# SCH_ESP_toster_GPIOv2.net
KiCad netlist of a schematic drawn in EasyEDA
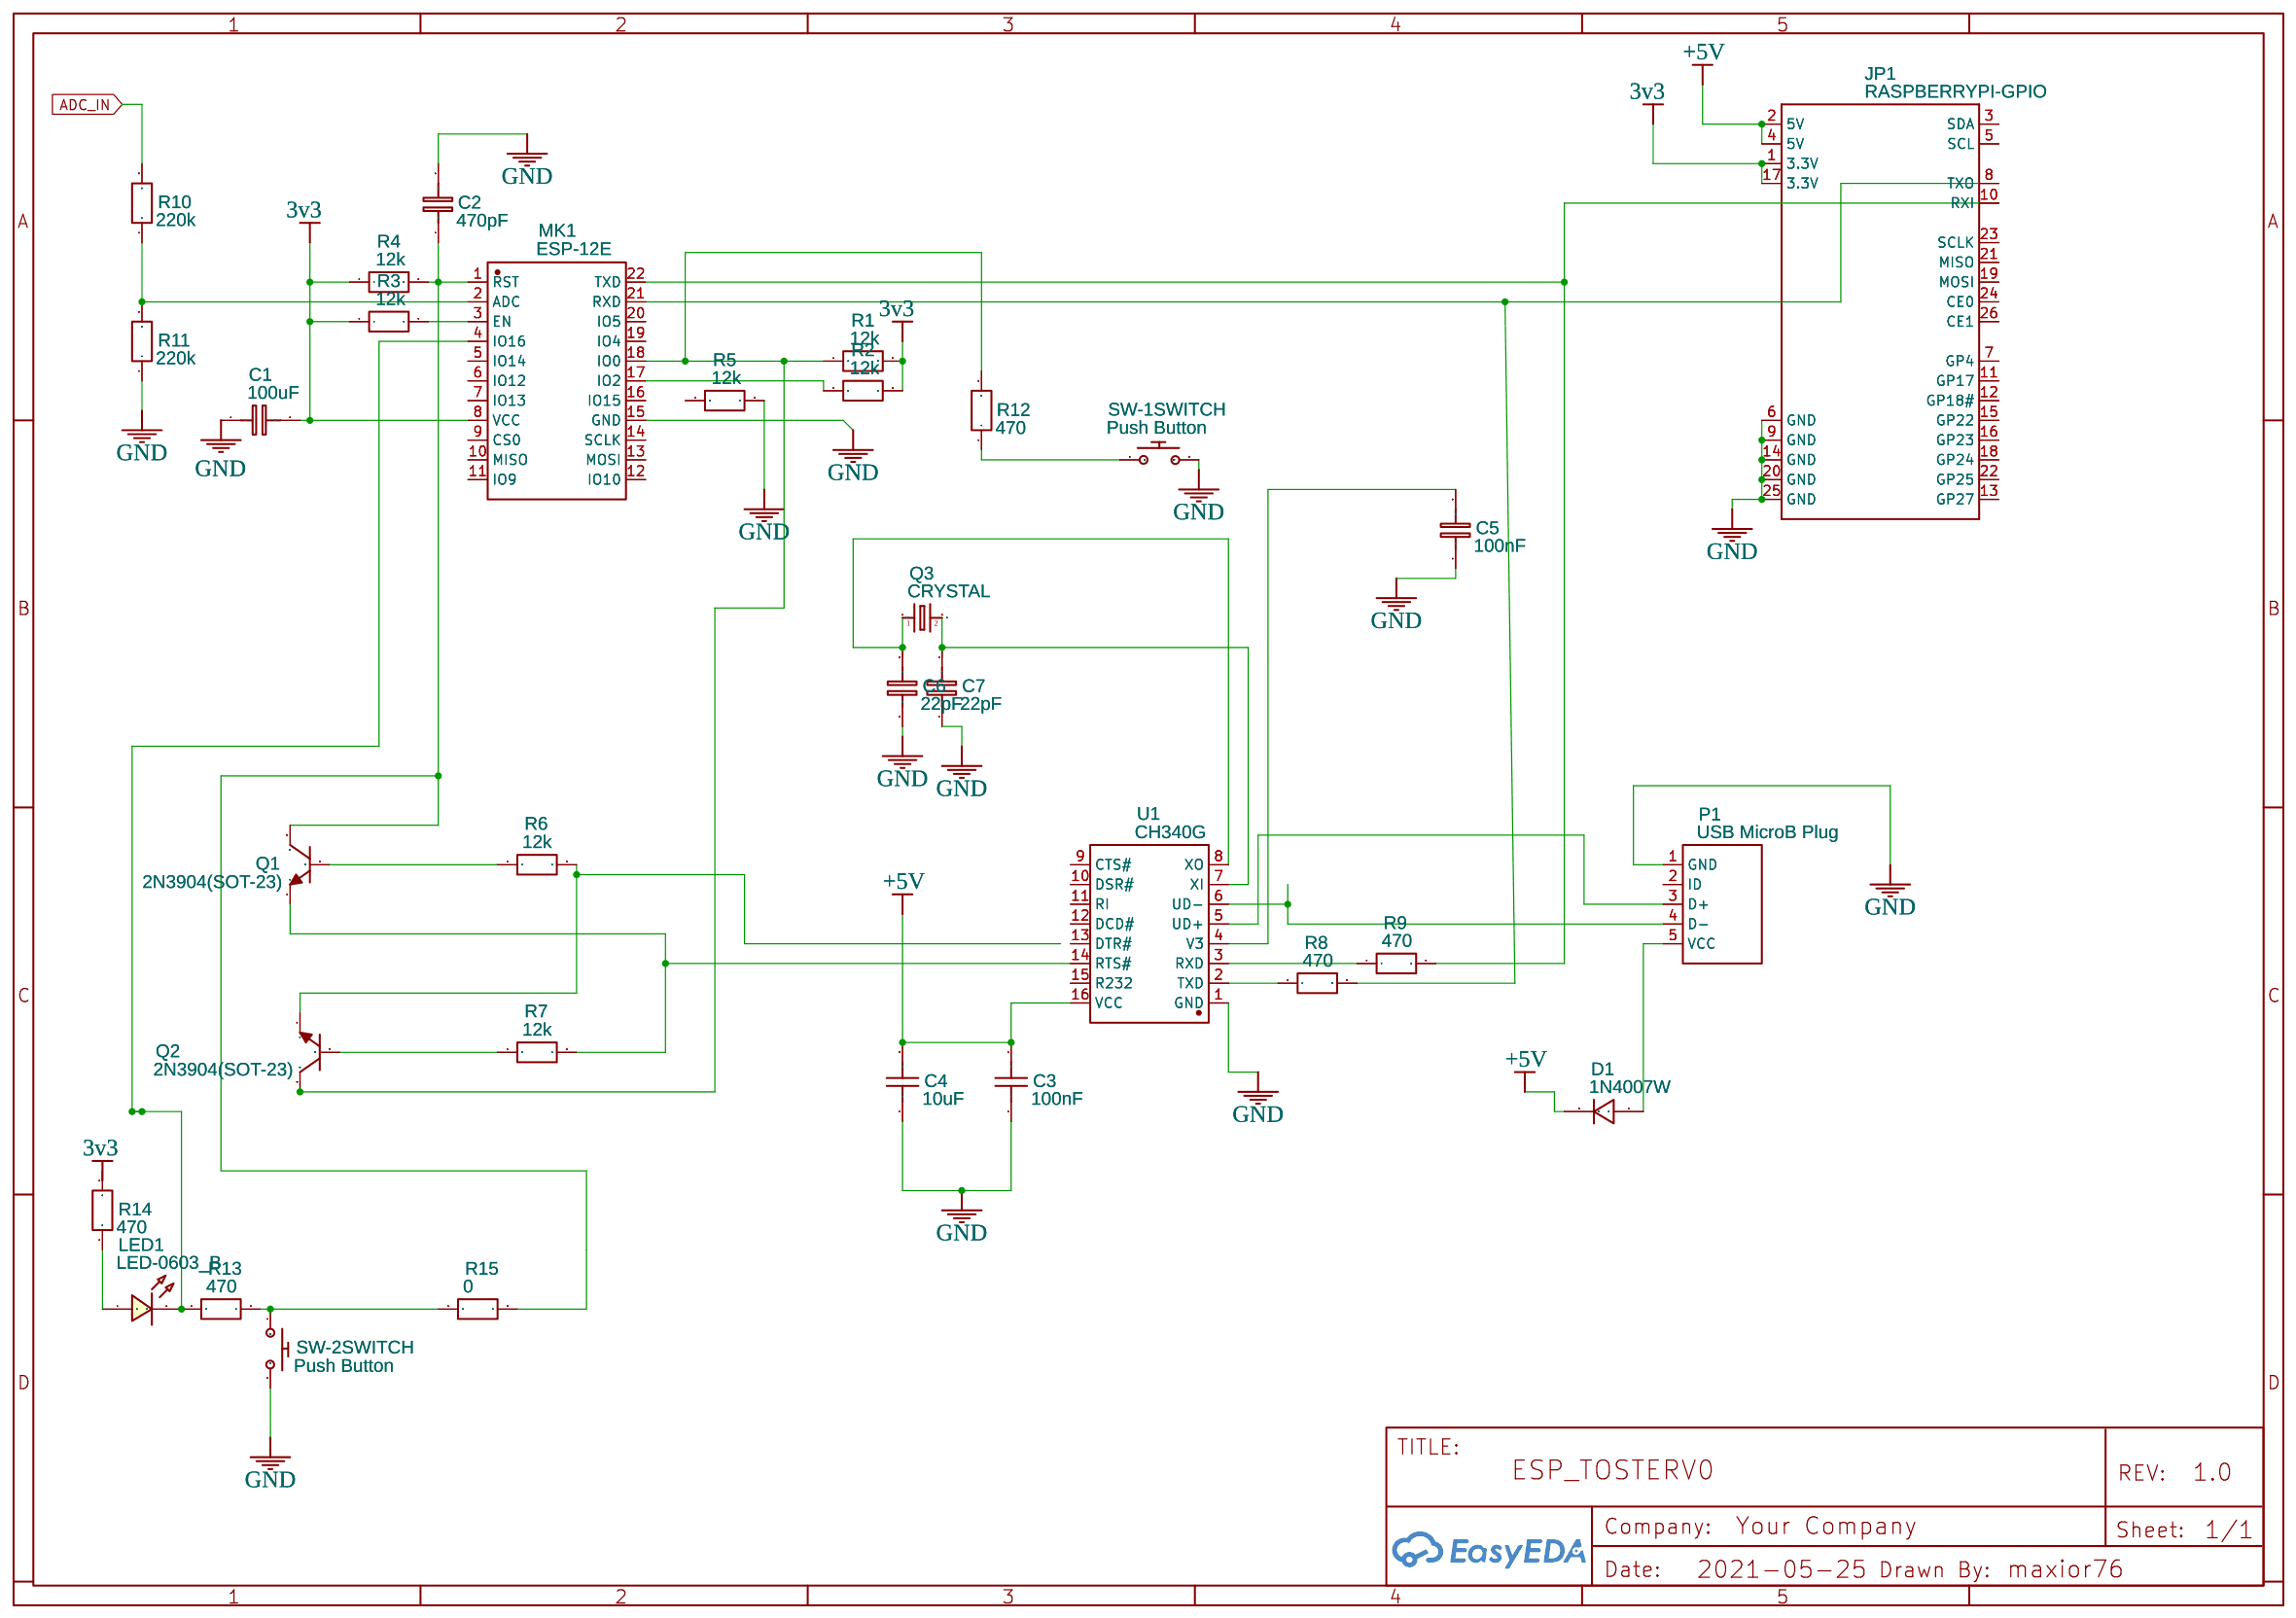
[diagram p0: schematic sheet]

(export (version "E")
  (design (tool "Eeschema 10.0.6"))
  (components
    (comp (ref "C1") (value "100uF") (libsource (lib "") (part "C_0603_EU_3")))
    (comp (ref "C2") (value "470pF") (libsource (lib "") (part "C_0603_EU")))
    (comp (ref "C3") (value "100nF") (libsource (lib "") (part "C_0603_US")))
    (comp (ref "C4") (value "10uF") (libsource (lib "") (part "C_0603_US")))
    (comp (ref "C5") (value "100nF") (libsource (lib "") (part "C_0603_EU_2")))
    (comp (ref "C6") (value "22pF") (libsource (lib "") (part "C_0603_EU_1")))
    (comp (ref "C7") (value "22pF") (libsource (lib "") (part "C_0603_EU_1")))
    (comp (ref "D1")
      (value "1N4007W")
      (fields (field (name "BOM_Supplier Part") "C328592"))
      (libsource (lib "") (part "1N4007W"))
    )
    (comp (ref "JP1") (value "RASPBERRYPI-GPIO") (libsource (lib "") (part "RASPBERRYPI-GPIO")))
    (comp (ref "LED1")
      (value "LED-0603_B")
      (fields
        (field (name "BOM_Manufacturer Part") "19-217/R6C-AL1M2VY/3T")
        (field (name "BOM_Supplier Part") "C72044")
      )
      (libsource (lib "") (part "LED-0603_R"))
    )
    (comp (ref "MK1")
      (value "ESP-12E")
      (fields (field (name "BOM_Supplier Part") "C89297"))
      (libsource (lib "") (part "ESP-12E"))
    )
    (comp (ref "P1") (value "USB MicroB Plug") (libsource (lib "") (part "USB MicroB Plug")))
    (comp (ref "Q1")
      (value "2N3904(SOT-23)")
      (fields
        (field (name "BOM_Manufacturer Part") "2n3904S-RTK/PS")
        (field (name "BOM_Supplier Part") "C18536")
      )
      (libsource (lib "") (part "2N3904(SOT-23)_1"))
    )
    (comp (ref "Q2")
      (value "2N3904(SOT-23)")
      (fields
        (field (name "BOM_Manufacturer Part") "2n3904S-RTK/PS")
        (field (name "BOM_Supplier Part") "C18536")
      )
      (libsource (lib "") (part "2N3904(SOT-23)"))
    )
    (comp (ref "Q3") (value "CRYSTAL") (libsource (lib "") (part "CRYSTAL")))
    (comp (ref "R1") (value "12k") (libsource (lib "") (part "R_0603_EU_1")))
    (comp (ref "R2") (value "12k") (libsource (lib "") (part "R_0603_EU_1")))
    (comp (ref "R3") (value "12k") (libsource (lib "") (part "R_0603_EU_1")))
    (comp (ref "R4") (value "12k") (libsource (lib "") (part "R_0603_EU_1")))
    (comp (ref "R5") (value "12k") (libsource (lib "") (part "R_0603_EU_1")))
    (comp (ref "R6") (value "12k") (libsource (lib "") (part "R_0603_EU_1")))
    (comp (ref "R7") (value "12k") (libsource (lib "") (part "R_0603_EU_1")))
    (comp (ref "R8") (value "470") (libsource (lib "") (part "R_0603_EU_1")))
    (comp (ref "R9") (value "470") (libsource (lib "") (part "R_0603_EU_1")))
    (comp (ref "R10") (value "220k") (libsource (lib "") (part "R_0603_EU")))
    (comp (ref "R11") (value "220k") (libsource (lib "") (part "R_0603_EU")))
    (comp (ref "R12") (value "470") (libsource (lib "") (part "R_0603_EU")))
    (comp (ref "R13") (value "470") (libsource (lib "") (part "R_0603_EU_1")))
    (comp (ref "R14") (value "470") (libsource (lib "") (part "R_0603_EU")))
    (comp (ref "R15") (value "0") (libsource (lib "") (part "R_0603_EU_1")))
    (comp (ref "SW-1SWITCH")
      (value "Push Button")
      (fields (field (name "BOM_Supplier Part") "COM-08720"))
      (libsource (lib "") (part "Push Button_1"))
    )
    (comp (ref "SW-2SWITCH")
      (value "Push Button")
      (fields (field (name "BOM_Supplier Part") "COM-08720"))
      (libsource (lib "") (part "Push Button"))
    )
    (comp (ref "U1")
      (value "CH340G")
      (fields (field (name "BOM_Supplier Part") "C14267"))
      (libsource (lib "") (part "CH340G"))
    )
  )
  (nets
    (net (code "1") (name "+5V") (class "Default")
      (node (ref "C3") (pin "2") (pinfunction "2_2") (pintype "unspecified"))
      (node (ref "C4") (pin "2") (pinfunction "2_2") (pintype "unspecified"))
      (node (ref "D1") (pin "1") (pinfunction "1_1") (pintype "unspecified"))
      (node (ref "JP1") (pin "2") (pinfunction "5V_2") (pintype "passive"))
      (node (ref "JP1") (pin "4") (pinfunction "5V_4") (pintype "passive"))
      (node (ref "U1") (pin "16") (pinfunction "VCC_16") (pintype "unspecified"))
    )
    (net (code "2") (name "3v3") (class "Default")
      (node (ref "C1") (pin "2") (pinfunction "2_2") (pintype "unspecified"))
      (node (ref "JP1") (pin "1") (pinfunction "3.3V_1") (pintype "passive"))
      (node (ref "JP1") (pin "17") (pinfunction "3.3V_17") (pintype "passive"))
      (node (ref "MK1") (pin "8") (pinfunction "VCC_8") (pintype "unspecified"))
      (node (ref "R1") (pin "2") (pinfunction "2_2") (pintype "unspecified"))
      (node (ref "R14") (pin "2") (pinfunction "2_2") (pintype "unspecified"))
      (node (ref "R2") (pin "2") (pinfunction "2_2") (pintype "unspecified"))
      (node (ref "R3") (pin "1") (pinfunction "1_1") (pintype "unspecified"))
      (node (ref "R4") (pin "1") (pinfunction "1_1") (pintype "unspecified"))
    )
    (net (code "3") (name "ADC_IN") (class "Default")
      (node (ref "R10") (pin "2") (pinfunction "2_2") (pintype "unspecified"))
    )
    (net (code "4") (name "GND") (class "Default")
      (node (ref "C1") (pin "1") (pinfunction "1_1") (pintype "unspecified"))
      (node (ref "C2") (pin "2") (pinfunction "2_2") (pintype "unspecified"))
      (node (ref "C3") (pin "1") (pinfunction "1_1") (pintype "unspecified"))
      (node (ref "C4") (pin "1") (pinfunction "1_1") (pintype "unspecified"))
      (node (ref "C5") (pin "1") (pinfunction "1_1") (pintype "unspecified"))
      (node (ref "C6") (pin "1") (pinfunction "1_1") (pintype "unspecified"))
      (node (ref "C7") (pin "1") (pinfunction "1_1") (pintype "unspecified"))
      (node (ref "JP1") (pin "14") (pinfunction "GND_14") (pintype "passive"))
      (node (ref "JP1") (pin "20") (pinfunction "GND_20") (pintype "passive"))
      (node (ref "JP1") (pin "25") (pinfunction "GND_25") (pintype "passive"))
      (node (ref "JP1") (pin "6") (pinfunction "GND_6") (pintype "passive"))
      (node (ref "JP1") (pin "9") (pinfunction "GND_9") (pintype "passive"))
      (node (ref "MK1") (pin "15") (pinfunction "GND_15") (pintype "unspecified"))
      (node (ref "P1") (pin "1") (pinfunction "GND_1") (pintype "unspecified"))
      (node (ref "R11") (pin "1") (pinfunction "1_1") (pintype "unspecified"))
      (node (ref "R5") (pin "2") (pinfunction "2_2") (pintype "unspecified"))
      (node (ref "SW-1SWITCH") (pin "2") (pinfunction "P$2_2") (pintype "unspecified"))
      (node (ref "SW-2SWITCH") (pin "2") (pinfunction "P$2_2") (pintype "unspecified"))
      (node (ref "U1") (pin "1") (pinfunction "GND_1") (pintype "unspecified"))
    )
    (net (code "5") (name "Net-(JP1-RXI)") (class "Default")
      (node (ref "JP1") (pin "10") (pinfunction "RXI_10") (pintype "input"))
      (node (ref "MK1") (pin "22") (pinfunction "TXD_22") (pintype "unspecified"))
      (node (ref "R9") (pin "2") (pinfunction "2_2") (pintype "unspecified"))
    )
    (net (code "6") (name "Net-(JP1-TXO)") (class "Default")
      (node (ref "JP1") (pin "8") (pinfunction "TXO_8") (pintype "output"))
      (node (ref "MK1") (pin "21") (pinfunction "RXD_21") (pintype "unspecified"))
      (node (ref "R8") (pin "2") (pinfunction "2_2") (pintype "unspecified"))
    )
    (net (code "7") (name "Net-(LED1-Pad1)") (class "Default")
      (node (ref "LED1") (pin "1") (pinfunction "1_1") (pintype "unspecified"))
      (node (ref "R14") (pin "1") (pinfunction "1_1") (pintype "unspecified"))
    )
    (net (code "8") (name "Net-(MK1-ADC)") (class "Default")
      (node (ref "MK1") (pin "2") (pinfunction "ADC_2") (pintype "unspecified"))
      (node (ref "R10") (pin "1") (pinfunction "1_1") (pintype "unspecified"))
      (node (ref "R11") (pin "2") (pinfunction "2_2") (pintype "unspecified"))
    )
    (net (code "9") (name "Net-(MK1-EN)") (class "Default")
      (node (ref "MK1") (pin "3") (pinfunction "EN_3") (pintype "unspecified"))
      (node (ref "R3") (pin "2") (pinfunction "2_2") (pintype "unspecified"))
    )
    (net (code "10") (name "Net-(MK1-IO0)") (class "Default")
      (node (ref "MK1") (pin "18") (pinfunction "IO0_18") (pintype "unspecified"))
      (node (ref "Q2") (pin "3") (pinfunction "C_3") (pintype "input"))
      (node (ref "R1") (pin "1") (pinfunction "1_1") (pintype "unspecified"))
      (node (ref "R12") (pin "2") (pinfunction "2_2") (pintype "unspecified"))
    )
    (net (code "11") (name "Net-(MK1-IO2)") (class "Default")
      (node (ref "MK1") (pin "17") (pinfunction "IO2_17") (pintype "unspecified"))
      (node (ref "R2") (pin "1") (pinfunction "1_1") (pintype "unspecified"))
    )
    (net (code "12") (name "Net-(MK1-IO16)") (class "Default")
      (node (ref "LED1") (pin "2") (pinfunction "2_2") (pintype "unspecified"))
      (node (ref "MK1") (pin "4") (pinfunction "IO16_4") (pintype "unspecified"))
      (node (ref "R13") (pin "1") (pinfunction "1_1") (pintype "unspecified"))
    )
    (net (code "13") (name "Net-(MK1-RST)") (class "Default")
      (node (ref "C2") (pin "1") (pinfunction "1_1") (pintype "unspecified"))
      (node (ref "MK1") (pin "1") (pinfunction "RST_1") (pintype "unspecified"))
      (node (ref "Q1") (pin "3") (pinfunction "C_3") (pintype "input"))
      (node (ref "R15") (pin "2") (pinfunction "2_2") (pintype "unspecified"))
      (node (ref "R4") (pin "2") (pinfunction "2_2") (pintype "unspecified"))
    )
    (net (code "14") (name "Net-(P1-D+)") (class "Default")
      (node (ref "P1") (pin "3") (pinfunction "D+_3") (pintype "unspecified"))
      (node (ref "U1") (pin "5") (pinfunction "UD+_5") (pintype "unspecified"))
    )
    (net (code "15") (name "Net-(P1-D-)") (class "Default")
      (node (ref "P1") (pin "4") (pinfunction "D-_4") (pintype "unspecified"))
      (node (ref "U1") (pin "6") (pinfunction "UD-_6") (pintype "unspecified"))
    )
    (net (code "16") (name "Net-(P1-VCC)") (class "Default")
      (node (ref "D1") (pin "2") (pinfunction "2_2") (pintype "unspecified"))
      (node (ref "P1") (pin "5") (pinfunction "VCC_5") (pintype "unspecified"))
    )
    (net (code "17") (name "Net-(Q1-B)") (class "Default")
      (node (ref "Q1") (pin "2") (pinfunction "B_2") (pintype "input"))
      (node (ref "R6") (pin "1") (pinfunction "1_1") (pintype "unspecified"))
    )
    (net (code "18") (name "Net-(Q1-E)") (class "Default")
      (node (ref "Q1") (pin "1") (pinfunction "E_1") (pintype "input"))
      (node (ref "R7") (pin "2") (pinfunction "2_2") (pintype "unspecified"))
      (node (ref "U1") (pin "14") (pinfunction "RTS#_14") (pintype "unspecified"))
    )
    (net (code "19") (name "Net-(Q2-B)") (class "Default")
      (node (ref "Q2") (pin "2") (pinfunction "B_2") (pintype "input"))
      (node (ref "R7") (pin "1") (pinfunction "1_1") (pintype "unspecified"))
    )
    (net (code "20") (name "Net-(Q2-E)") (class "Default")
      (node (ref "Q2") (pin "1") (pinfunction "E_1") (pintype "input"))
      (node (ref "R6") (pin "2") (pinfunction "2_2") (pintype "unspecified"))
    )
    (net (code "21") (name "Net-(SW-1SWITCH-P$1)") (class "Default")
      (node (ref "R12") (pin "1") (pinfunction "1_1") (pintype "unspecified"))
      (node (ref "SW-1SWITCH") (pin "1") (pinfunction "P$1_1") (pintype "unspecified"))
    )
    (net (code "22") (name "Net-(SW-2SWITCH-P$1)") (class "Default")
      (node (ref "R13") (pin "2") (pinfunction "2_2") (pintype "unspecified"))
      (node (ref "R15") (pin "1") (pinfunction "1_1") (pintype "unspecified"))
      (node (ref "SW-2SWITCH") (pin "1") (pinfunction "P$1_1") (pintype "unspecified"))
    )
    (net (code "23") (name "Net-(U1-RXD)") (class "Default")
      (node (ref "R9") (pin "1") (pinfunction "1_1") (pintype "unspecified"))
      (node (ref "U1") (pin "3") (pinfunction "RXD_3") (pintype "unspecified"))
    )
    (net (code "24") (name "Net-(U1-TXD)") (class "Default")
      (node (ref "R8") (pin "1") (pinfunction "1_1") (pintype "unspecified"))
      (node (ref "U1") (pin "2") (pinfunction "TXD_2") (pintype "unspecified"))
    )
    (net (code "25") (name "Net-(U1-V3)") (class "Default")
      (node (ref "C5") (pin "2") (pinfunction "2_2") (pintype "unspecified"))
      (node (ref "U1") (pin "4") (pinfunction "V3_4") (pintype "unspecified"))
    )
    (net (code "26") (name "Net-(U1-XI)") (class "Default")
      (node (ref "C7") (pin "2") (pinfunction "2_2") (pintype "unspecified"))
      (node (ref "Q3") (pin "2") (pinfunction "2_2") (pintype "unspecified"))
      (node (ref "U1") (pin "7") (pinfunction "XI_7") (pintype "unspecified"))
    )
    (net (code "27") (name "Net-(U1-XO)") (class "Default")
      (node (ref "C6") (pin "2") (pinfunction "2_2") (pintype "unspecified"))
      (node (ref "Q3") (pin "1") (pinfunction "1_1") (pintype "unspecified"))
      (node (ref "U1") (pin "8") (pinfunction "XO_8") (pintype "unspecified"))
    )
    (net (code "28") (name "unconnected-(JP1-CE0-Pad24)") (class "Default")
      (node (ref "JP1") (pin "24") (pinfunction "CE0_24") (pintype "output"))
    )
    (net (code "29") (name "unconnected-(JP1-CE1-Pad26)") (class "Default")
      (node (ref "JP1") (pin "26") (pinfunction "CE1_26") (pintype "output"))
    )
    (net (code "30") (name "unconnected-(JP1-GP4-Pad7)") (class "Default")
      (node (ref "JP1") (pin "7") (pinfunction "GP4_7") (pintype "unspecified"))
    )
    (net (code "31") (name "unconnected-(JP1-GP17-Pad11)") (class "Default")
      (node (ref "JP1") (pin "11") (pinfunction "GP17_11") (pintype "unspecified"))
    )
    (net (code "32") (name "unconnected-(JP1-GP18#-Pad12)") (class "Default")
      (node (ref "JP1") (pin "12") (pinfunction "GP18#_12") (pintype "unspecified"))
    )
    (net (code "33") (name "unconnected-(JP1-GP22-Pad15)") (class "Default")
      (node (ref "JP1") (pin "15") (pinfunction "GP22_15") (pintype "unspecified"))
    )
    (net (code "34") (name "unconnected-(JP1-GP23-Pad16)") (class "Default")
      (node (ref "JP1") (pin "16") (pinfunction "GP23_16") (pintype "unspecified"))
    )
    (net (code "35") (name "unconnected-(JP1-GP24-Pad18)") (class "Default")
      (node (ref "JP1") (pin "18") (pinfunction "GP24_18") (pintype "unspecified"))
    )
    (net (code "36") (name "unconnected-(JP1-GP25-Pad22)") (class "Default")
      (node (ref "JP1") (pin "22") (pinfunction "GP25_22") (pintype "unspecified"))
    )
    (net (code "37") (name "unconnected-(JP1-GP27-Pad13)") (class "Default")
      (node (ref "JP1") (pin "13") (pinfunction "GP27_13") (pintype "unspecified"))
    )
    (net (code "38") (name "unconnected-(JP1-MISO-Pad21)") (class "Default")
      (node (ref "JP1") (pin "21") (pinfunction "MISO_21") (pintype "input"))
    )
    (net (code "39") (name "unconnected-(JP1-MOSI-Pad19)") (class "Default")
      (node (ref "JP1") (pin "19") (pinfunction "MOSI_19") (pintype "output"))
    )
    (net (code "40") (name "unconnected-(JP1-SCL-Pad5)") (class "Default")
      (node (ref "JP1") (pin "5") (pinfunction "SCL_5") (pintype "unspecified"))
    )
    (net (code "41") (name "unconnected-(JP1-SCLK-Pad23)") (class "Default")
      (node (ref "JP1") (pin "23") (pinfunction "SCLK_23") (pintype "output"))
    )
    (net (code "42") (name "unconnected-(JP1-SDA-Pad3)") (class "Default")
      (node (ref "JP1") (pin "3") (pinfunction "SDA_3") (pintype "unspecified"))
    )
    (net (code "43") (name "unconnected-(MK1-CS0-Pad9)") (class "Default")
      (node (ref "MK1") (pin "9") (pinfunction "CS0_9") (pintype "unspecified"))
    )
    (net (code "44") (name "unconnected-(MK1-IO4-Pad19)") (class "Default")
      (node (ref "MK1") (pin "19") (pinfunction "IO4_19") (pintype "unspecified"))
    )
    (net (code "45") (name "unconnected-(MK1-IO5-Pad20)") (class "Default")
      (node (ref "MK1") (pin "20") (pinfunction "IO5_20") (pintype "unspecified"))
    )
    (net (code "46") (name "unconnected-(MK1-IO9-Pad11)") (class "Default")
      (node (ref "MK1") (pin "11") (pinfunction "IO9_11") (pintype "unspecified"))
    )
    (net (code "47") (name "unconnected-(MK1-IO10-Pad12)") (class "Default")
      (node (ref "MK1") (pin "12") (pinfunction "IO10_12") (pintype "unspecified"))
    )
    (net (code "48") (name "unconnected-(MK1-IO12-Pad6)") (class "Default")
      (node (ref "MK1") (pin "6") (pinfunction "IO12_6") (pintype "unspecified"))
    )
    (net (code "49") (name "unconnected-(MK1-IO13-Pad7)") (class "Default")
      (node (ref "MK1") (pin "7") (pinfunction "IO13_7") (pintype "unspecified"))
    )
    (net (code "50") (name "unconnected-(MK1-IO14-Pad5)") (class "Default")
      (node (ref "MK1") (pin "5") (pinfunction "IO14_5") (pintype "unspecified"))
    )
    (net (code "51") (name "unconnected-(MK1-IO15-Pad16)") (class "Default")
      (node (ref "MK1") (pin "16") (pinfunction "IO15_16") (pintype "unspecified"))
    )
    (net (code "52") (name "unconnected-(MK1-MISO-Pad10)") (class "Default")
      (node (ref "MK1") (pin "10") (pinfunction "MISO_10") (pintype "unspecified"))
    )
    (net (code "53") (name "unconnected-(MK1-MOSI-Pad13)") (class "Default")
      (node (ref "MK1") (pin "13") (pinfunction "MOSI_13") (pintype "unspecified"))
    )
    (net (code "54") (name "unconnected-(MK1-SCLK-Pad14)") (class "Default")
      (node (ref "MK1") (pin "14") (pinfunction "SCLK_14") (pintype "unspecified"))
    )
    (net (code "55") (name "unconnected-(P1-ID-Pad2)") (class "Default")
      (node (ref "P1") (pin "2") (pinfunction "ID_2") (pintype "unspecified"))
    )
    (net (code "56") (name "unconnected-(R5-Pad1)") (class "Default")
      (node (ref "R5") (pin "1") (pinfunction "1_1") (pintype "unspecified"))
    )
    (net (code "57") (name "unconnected-(U1-CTS#-Pad9)") (class "Default")
      (node (ref "U1") (pin "9") (pinfunction "CTS#_9") (pintype "unspecified"))
    )
    (net (code "58") (name "unconnected-(U1-DCD#-Pad12)") (class "Default")
      (node (ref "U1") (pin "12") (pinfunction "DCD#_12") (pintype "unspecified"))
    )
    (net (code "59") (name "unconnected-(U1-DSR#-Pad10)") (class "Default")
      (node (ref "U1") (pin "10") (pinfunction "DSR#_10") (pintype "unspecified"))
    )
    (net (code "60") (name "unconnected-(U1-DTR#-Pad13)") (class "Default")
      (node (ref "U1") (pin "13") (pinfunction "DTR#_13") (pintype "unspecified"))
    )
    (net (code "61") (name "unconnected-(U1-R232-Pad15)") (class "Default")
      (node (ref "U1") (pin "15") (pinfunction "R232_15") (pintype "unspecified"))
    )
    (net (code "62") (name "unconnected-(U1-RI-Pad11)") (class "Default")
      (node (ref "U1") (pin "11") (pinfunction "RI_11") (pintype "unspecified"))
    )
  )
)
